# controller_board.net
KiCad netlist of a schematic drawn in EAGLE
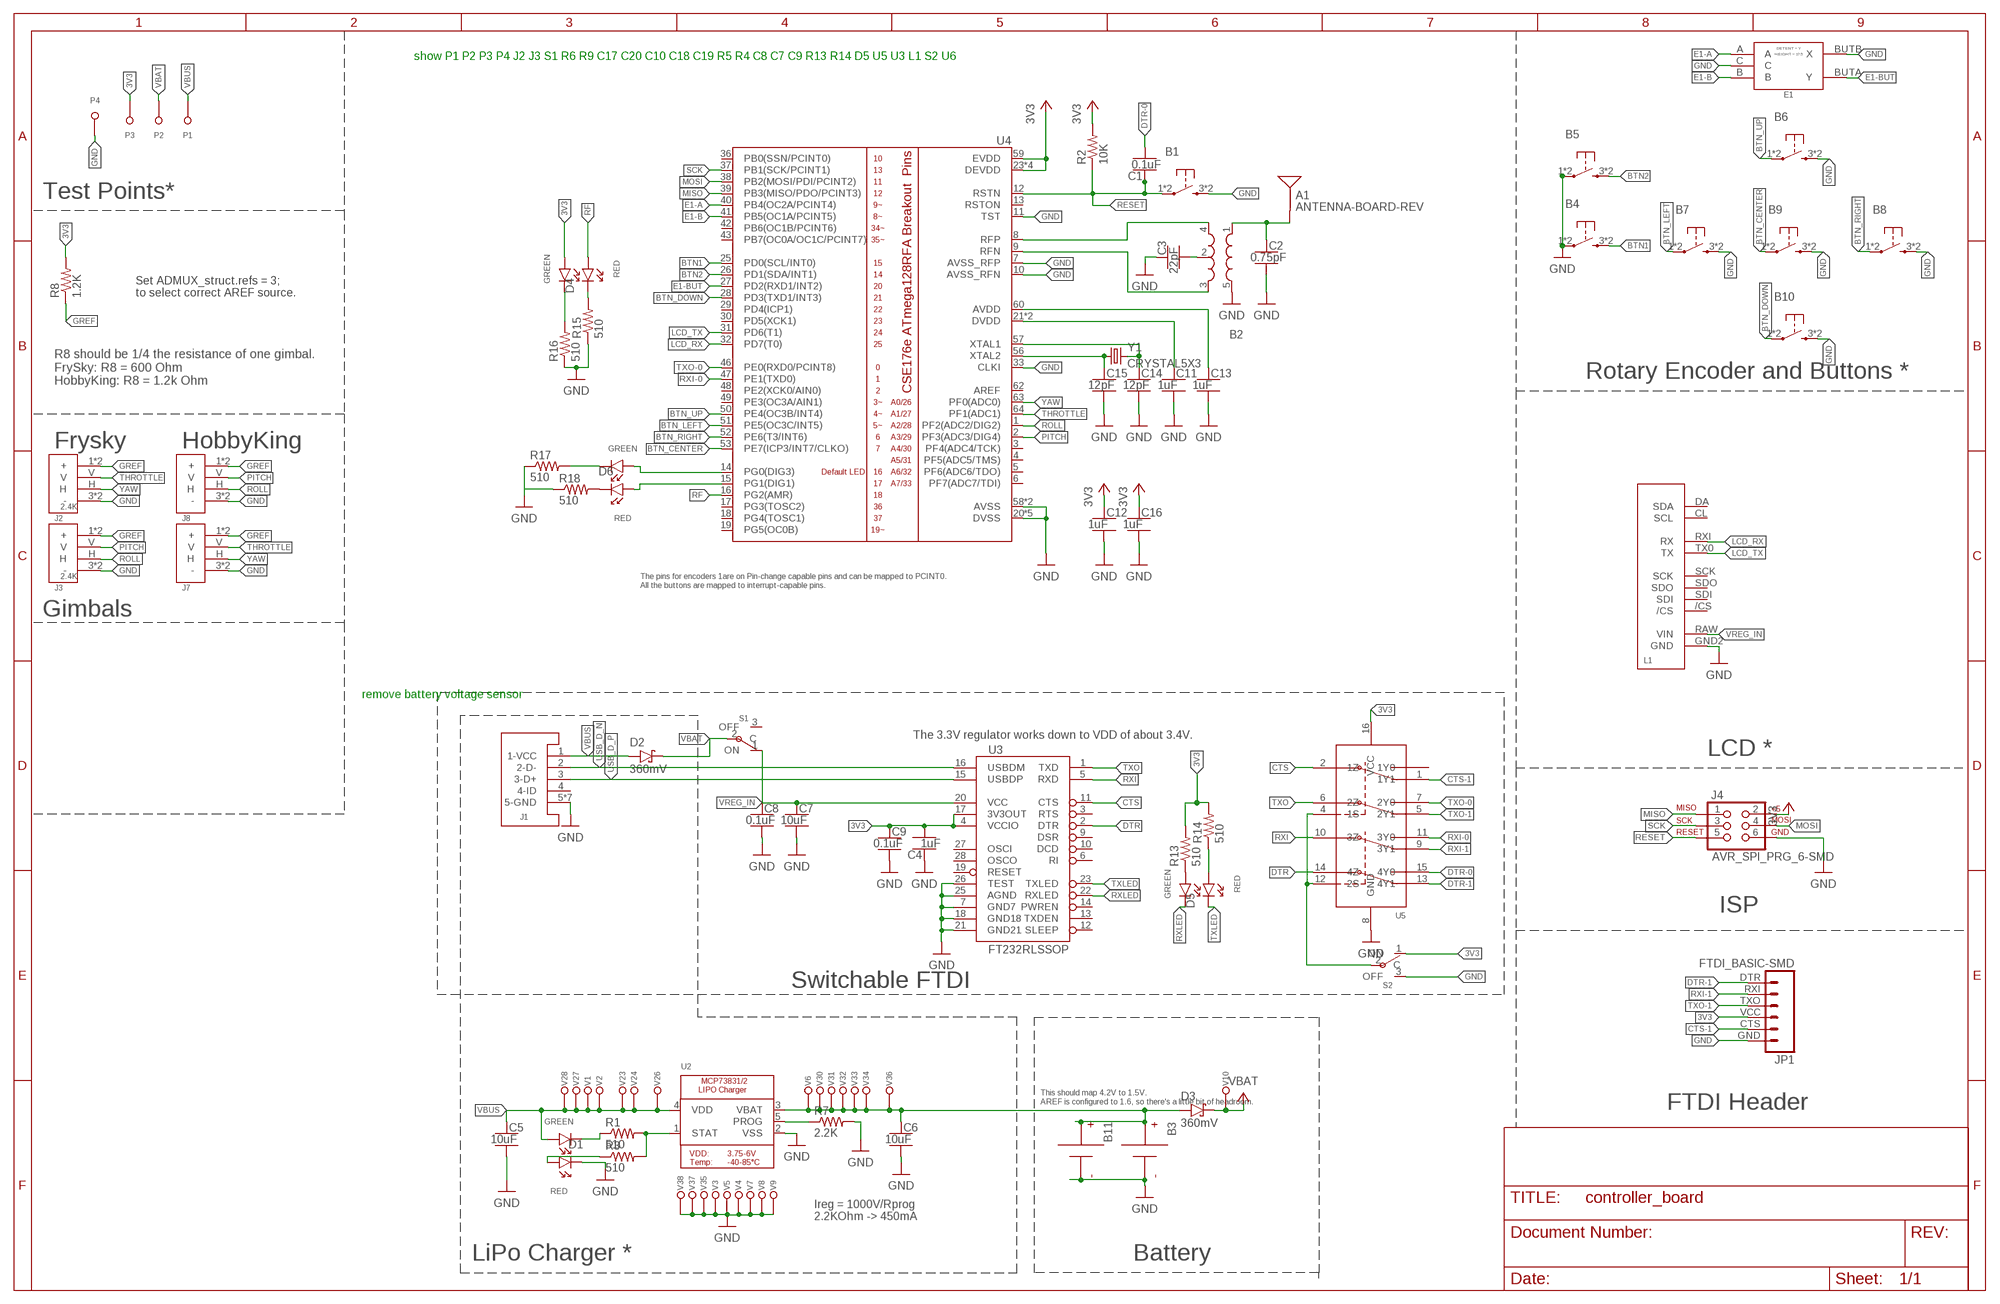
[diagram p0: schematic, sheet 1]

(export (version "E")
  (design (tool "Eeschema 10.0.6"))
  (components
    (comp (ref "A1")
      (value "ANTENNA-BOARD-REV")
      (footprint "eagle-import:ANT_PCB_2.4GHZ_NRF8001_1.6MM_1OZ_REV")
      (fields (field (name "CREATOR") "Swanson"))
      (libsource (lib "eagle-import") (part "ANTENNA-BOARD-REV"))
    )
    (comp (ref "B1")
      (value "PUSHBUTTON_-4.5X4.5")
      (footprint "eagle-import:4.5MM_TACTILE_SWITCH_TL3305AF160QG")
      (fields (field (name "CREATOR") "Swanson"))
      (libsource (lib "eagle-import") (part "PUSHBUTTON_-4.5X4.5"))
    )
    (comp (ref "B2")
      (value "BALUN0805")
      (footprint "eagle-import:BALUN")
      (fields
        (field (name "MFR") "Wurth Electronics Inc")
        (field (name "MPN") "748421245")
        (field (name "CREATOR") "Swanson")
        (field (name "REVIEWER") "Swanson")
      )
      (libsource (lib "eagle-import") (part "BALUN0805"))
    )
    (comp (ref "B3")
      (value "BATTERY-SPRING-SMD")
      (footprint "eagle-import:WIRE-TERMINAL-1X2-2.5MM-SMD-AVX-009276002021106")
      (libsource (lib "eagle-import") (part "BATTERY-SPRING-SMD"))
    )
    (comp (ref "B4")
      (value "PUSHBUTTON_-4.5X4.5")
      (footprint "eagle-import:4.5MM_TACTILE_SWITCH_TL3305AF160QG")
      (fields (field (name "CREATOR") "Swanson"))
      (libsource (lib "eagle-import") (part "PUSHBUTTON_-4.5X4.5"))
    )
    (comp (ref "B5")
      (value "PUSHBUTTON_-4.5X4.5")
      (footprint "eagle-import:4.5MM_TACTILE_SWITCH_TL3305AF160QG")
      (fields (field (name "CREATOR") "Swanson"))
      (libsource (lib "eagle-import") (part "PUSHBUTTON_-4.5X4.5"))
    )
    (comp (ref "B6")
      (value "PUSHBUTTON_-4.5X4.5")
      (footprint "eagle-import:4.5MM_TACTILE_SWITCH_TL3305AF160QG")
      (fields (field (name "CREATOR") "Swanson"))
      (libsource (lib "eagle-import") (part "PUSHBUTTON_-4.5X4.5"))
    )
    (comp (ref "B7")
      (value "PUSHBUTTON_-4.5X4.5")
      (footprint "eagle-import:4.5MM_TACTILE_SWITCH_TL3305AF160QG")
      (fields (field (name "CREATOR") "Swanson"))
      (libsource (lib "eagle-import") (part "PUSHBUTTON_-4.5X4.5"))
    )
    (comp (ref "B8")
      (value "PUSHBUTTON_-4.5X4.5")
      (footprint "eagle-import:4.5MM_TACTILE_SWITCH_TL3305AF160QG")
      (fields (field (name "CREATOR") "Swanson"))
      (libsource (lib "eagle-import") (part "PUSHBUTTON_-4.5X4.5"))
    )
    (comp (ref "B9")
      (value "PUSHBUTTON_-4.5X4.5")
      (footprint "eagle-import:4.5MM_TACTILE_SWITCH_TL3305AF160QG")
      (fields (field (name "CREATOR") "Swanson"))
      (libsource (lib "eagle-import") (part "PUSHBUTTON_-4.5X4.5"))
    )
    (comp (ref "B10")
      (value "PUSHBUTTON_-4.5X4.5")
      (footprint "eagle-import:4.5MM_TACTILE_SWITCH_TL3305AF160QG")
      (fields (field (name "CREATOR") "Swanson"))
      (libsource (lib "eagle-import") (part "PUSHBUTTON_-4.5X4.5"))
    )
    (comp (ref "B11")
      (value "BATTERY-SCREW-TERMINAL")
      (footprint "eagle-import:SCREW-TERMINAL-1X2-2.54MM")
      (fields (field (name "CREATOR") "Swanson"))
      (libsource (lib "eagle-import") (part "BATTERY-SCREW-TERMINAL"))
    )
    (comp (ref "C1")
      (value "0.1uF")
      (footprint "eagle-import:CAPC2012X140_HS")
      (fields
        (field (name "MFR") "TDK")
        (field (name "MPN") "C2012X7R2A104K125AA")
        (field (name "CREATOR") "Swanson")
        (field (name "REVIEWER") "Swanson")
      )
      (libsource (lib "eagle-import") (part "CAPACITOR-NP_SMD-2012-0805_CERAMIC-0.1UF"))
    )
    (comp (ref "C2")
      (value "0.75pF")
      (footprint "eagle-import:CAPC2012X140_HS")
      (fields
        (field (name "MFR") "Murata Electronics North America")
        (field (name "MPN") "GQM2195C2AR75CB01D")
        (field (name "CREATOR") "Swanson")
        (field (name "REVIEWER") "Swanson")
      )
      (libsource (lib "eagle-import") (part "CAPACITOR-NP_SMD-2012-0805_CERAMIC-0.75PF"))
    )
    (comp (ref "C3")
      (value "22pF")
      (footprint "eagle-import:CAPC2012X140_HS")
      (fields
        (field (name "MFR") "Murata Electronics North America")
        (field (name "MPN") "GRM21A5C2E220JW01D")
        (field (name "CREATOR") "Swanson")
        (field (name "REVIEWER") "Swanson")
      )
      (libsource (lib "eagle-import") (part "CAPACITOR-NP_SMD-2012-0805_CERAMIC-22PF"))
    )
    (comp (ref "C4")
      (value "1uF")
      (footprint "eagle-import:CAPC2012X140_HS")
      (fields
        (field (name "MFR") "Taiyo Yuden")
        (field (name "MPN") "TMK212B7105KG-T")
        (field (name "CREATOR") "Swanson")
        (field (name "REVIEWER") "Swanson")
      )
      (libsource (lib "eagle-import") (part "CAPACITOR-NP_SMD-2012-0805_CERAMIC-1UF"))
    )
    (comp (ref "C5")
      (value "10uF")
      (footprint "eagle-import:CAPC2012X140_HS")
      (fields (field (name "CREATOR") "Swanson") (field (name "REVIEWER") "Swanson"))
      (libsource (lib "eagle-import") (part "CAPACITOR-NP_SMD-2012-0805_CERAMIC-10UF"))
    )
    (comp (ref "C6")
      (value "10uF")
      (footprint "eagle-import:CAPC2012X140_HS")
      (fields (field (name "CREATOR") "Swanson") (field (name "REVIEWER") "Swanson"))
      (libsource (lib "eagle-import") (part "CAPACITOR-NP_SMD-2012-0805_CERAMIC-10UF"))
    )
    (comp (ref "C7")
      (value "10uF")
      (footprint "eagle-import:CAPC2012X140_HS")
      (fields (field (name "CREATOR") "Swanson") (field (name "REVIEWER") "Swanson"))
      (libsource (lib "eagle-import") (part "CAPACITOR-NP_SMD-2012-0805_CERAMIC-10UF"))
    )
    (comp (ref "C8")
      (value "0.1uF")
      (footprint "eagle-import:CAPC2012X140_HS")
      (fields
        (field (name "MFR") "TDK")
        (field (name "MPN") "C2012X7R2A104K125AA")
        (field (name "CREATOR") "Swanson")
        (field (name "REVIEWER") "Swanson")
      )
      (libsource (lib "eagle-import") (part "CAPACITOR-NP_SMD-2012-0805_CERAMIC-0.1UF"))
    )
    (comp (ref "C9")
      (value "0.1uF")
      (footprint "eagle-import:CAPC2012X140_HS")
      (fields
        (field (name "MFR") "TDK")
        (field (name "MPN") "C2012X7R2A104K125AA")
        (field (name "CREATOR") "Swanson")
        (field (name "REVIEWER") "Swanson")
      )
      (libsource (lib "eagle-import") (part "CAPACITOR-NP_SMD-2012-0805_CERAMIC-0.1UF"))
    )
    (comp (ref "C11")
      (value "1uF")
      (footprint "eagle-import:CAPC2012X140_HS")
      (fields
        (field (name "MFR") "Taiyo Yuden")
        (field (name "MPN") "TMK212B7105KG-T")
        (field (name "CREATOR") "Swanson")
        (field (name "REVIEWER") "Swanson")
      )
      (libsource (lib "eagle-import") (part "CAPACITOR-NP_SMD-2012-0805_CERAMIC-1UF"))
    )
    (comp (ref "C12")
      (value "1uF")
      (footprint "eagle-import:CAPC2012X140_HS")
      (fields
        (field (name "MFR") "Taiyo Yuden")
        (field (name "MPN") "TMK212B7105KG-T")
        (field (name "CREATOR") "Swanson")
        (field (name "REVIEWER") "Swanson")
      )
      (libsource (lib "eagle-import") (part "CAPACITOR-NP_SMD-2012-0805_CERAMIC-1UF"))
    )
    (comp (ref "C13")
      (value "1uF")
      (footprint "eagle-import:CAPC2012X140_HS")
      (fields
        (field (name "MFR") "Taiyo Yuden")
        (field (name "MPN") "TMK212B7105KG-T")
        (field (name "CREATOR") "Swanson")
        (field (name "REVIEWER") "Swanson")
      )
      (libsource (lib "eagle-import") (part "CAPACITOR-NP_SMD-2012-0805_CERAMIC-1UF"))
    )
    (comp (ref "C14")
      (value "12pF")
      (footprint "eagle-import:CAPC2012X140_HS")
      (fields
        (field (name "MFR") "Murata Electronics North America")
        (field (name "MPN") "GRM21A5C2E120JW01D")
        (field (name "CREATOR") "Swanson")
        (field (name "REVIEWER") "Swanson")
      )
      (libsource (lib "eagle-import") (part "CAPACITOR-NP_SMD-2012-0805_CERAMIC-12PF"))
    )
    (comp (ref "C15")
      (value "12pF")
      (footprint "eagle-import:CAPC2012X140_HS")
      (fields
        (field (name "MFR") "Murata Electronics North America")
        (field (name "MPN") "GRM21A5C2E120JW01D")
        (field (name "CREATOR") "Swanson")
        (field (name "REVIEWER") "Swanson")
      )
      (libsource (lib "eagle-import") (part "CAPACITOR-NP_SMD-2012-0805_CERAMIC-12PF"))
    )
    (comp (ref "C16")
      (value "1uF")
      (footprint "eagle-import:CAPC2012X140_HS")
      (fields
        (field (name "MFR") "Taiyo Yuden")
        (field (name "MPN") "TMK212B7105KG-T")
        (field (name "CREATOR") "Swanson")
        (field (name "REVIEWER") "Swanson")
      )
      (libsource (lib "eagle-import") (part "CAPACITOR-NP_SMD-2012-0805_CERAMIC-1UF"))
    )
    (comp (ref "D1")
      (value "LED-2X-GREEN/RED")
      (footprint "eagle-import:LED-2X-LTST-C155")
      (fields
        (field (name "COLOR2") "RED")
        (field (name "COLOR1") "GREEN")
        (field (name "CREATOR") "Swanson")
      )
      (libsource (lib "eagle-import") (part "LED-2X-GREEN/RED"))
    )
    (comp (ref "D2")
      (value "360mV")
      (footprint "eagle-import:SOD3716X135_HS")
      (fields
        (field (name "MFR") "Toshiba Semiconductor and Storage")
        (field (name "MPN") "CRS08(TE85L,Q,M)")
        (field (name "CREATOR") "Swanson")
        (field (name "REVIEWER") "Swanson")
      )
      (libsource (lib "eagle-import") (part "DIODE-SCHOTTKY_SMD-SOD123-360MV"))
    )
    (comp (ref "D3")
      (value "360mV")
      (footprint "eagle-import:SOD3716X135_HS")
      (fields
        (field (name "MFR") "Toshiba Semiconductor and Storage")
        (field (name "MPN") "CRS08(TE85L,Q,M)")
        (field (name "CREATOR") "Swanson")
        (field (name "REVIEWER") "Swanson")
      )
      (libsource (lib "eagle-import") (part "DIODE-SCHOTTKY_SMD-SOD123-360MV"))
    )
    (comp (ref "D4")
      (value "LED-2X-GREEN/RED")
      (footprint "eagle-import:LED-2X-LTST-C155")
      (fields
        (field (name "COLOR2") "RED")
        (field (name "COLOR1") "GREEN")
        (field (name "CREATOR") "Swanson")
      )
      (libsource (lib "eagle-import") (part "LED-2X-GREEN/RED"))
    )
    (comp (ref "D5")
      (value "LED-2X-GREEN/RED")
      (footprint "eagle-import:LED-2X-LTST-C155")
      (fields
        (field (name "COLOR2") "RED")
        (field (name "COLOR1") "GREEN")
        (field (name "CREATOR") "Swanson")
      )
      (libsource (lib "eagle-import") (part "LED-2X-GREEN/RED"))
    )
    (comp (ref "D6")
      (value "LED-2X-GREEN/RED")
      (footprint "eagle-import:LED-2X-LTST-C155")
      (fields
        (field (name "COLOR2") "RED")
        (field (name "COLOR1") "GREEN")
        (field (name "CREATOR") "Swanson")
      )
      (libsource (lib "eagle-import") (part "LED-2X-GREEN/RED"))
    )
    (comp (ref "E1")
      (value "ROTARY-ENCODER-W/BUTTON-BOURNS-PEC12R-4217F")
      (footprint "eagle-import:BOURNS-PEC12R")
      (fields (field (name "DETENT") "Y") (field (name "HEIGHT") "17.5") (field (name "CREATOR") "Swanson"))
      (libsource (lib "eagle-import") (part "ROTARY-ENCODER-W/BUTTON-BOURNS-PEC12R-4217F"))
    )
    (comp (ref "J1")
      (value "USB-MICROA-AMPHENOL-10118192-0001LF")
      (footprint "eagle-import:USB-MICROA-10118192-0001LF")
      (fields (field (name "CREATOR") "Swanson"))
      (libsource (lib "eagle-import") (part "USB-MICROA-AMPHENOL-10118192-0001LF"))
    )
    (comp (ref "J2")
      (value "2.4K")
      (footprint "eagle-import:JST-13-PTH")
      (fields (field (name "CREATOR") "Swanson"))
      (libsource (lib "eagle-import") (part "FRSKY-GIMBAL-FRYSKY"))
    )
    (comp (ref "J3")
      (value "2.4K")
      (footprint "eagle-import:JST-13-PTH")
      (fields (field (name "SPICEPREFIX") "E") (field (name "CREATOR") "Swanson"))
      (libsource (lib "eagle-import") (part "FRSKY-GIMBAL-FRYSKY"))
    )
    (comp (ref "J4")
      (value "AVR_SPI_PRG_6-SMD")
      (footprint "eagle-import:2X3-SMD")
      (fields (field (name "CREATOR") "Swanson"))
      (libsource (lib "eagle-import") (part "AVR_SPI_PRG_6-SMD"))
    )
    (comp (ref "J7")
      (value "FRSKY-GIMBAL-2X-SERVO-SMD")
      (footprint "eagle-import:2X-SERVO-SMD")
      (libsource (lib "eagle-import") (part "FRSKY-GIMBAL-2X-SERVO-SMD"))
    )
    (comp (ref "J8")
      (value "FRSKY-GIMBAL-2X-SERVO-SMD")
      (footprint "eagle-import:2X-SERVO-SMD")
      (libsource (lib "eagle-import") (part "FRSKY-GIMBAL-2X-SERVO-SMD"))
    )
    (comp (ref "JP1")
      (value "FTDI_BASIC-SMD")
      (footprint "eagle-import:FTDI-BASIC-SMD")
      (libsource (lib "eagle-import") (part "FTDI_BASIC-SMD"))
    )
    (comp (ref "L1")
      (value "SPARKFUN_SERLCD_SERIAL_REDUCED-SMD")
      (footprint "eagle-import:SPARKFUN_SERLCD_16X2_REDUCED_SMD")
      (fields (field (name "CREATOR") "Swanson"))
      (libsource (lib "eagle-import") (part "SPARKFUN_SERLCD_SERIAL_REDUCED-SMD"))
    )
    (comp (ref "P1")
      (value "TEST-POINT")
      (footprint "eagle-import:TEST-POINT-KEYSTONE-5000")
      (fields (field (name "CREATOR") "Swanson"))
      (libsource (lib "eagle-import") (part "TEST-POINT"))
    )
    (comp (ref "P2")
      (value "TEST-POINT")
      (footprint "eagle-import:TEST-POINT-KEYSTONE-5000")
      (fields (field (name "CREATOR") "Swanson"))
      (libsource (lib "eagle-import") (part "TEST-POINT"))
    )
    (comp (ref "P3")
      (value "TEST-POINT")
      (footprint "eagle-import:TEST-POINT-KEYSTONE-5000")
      (fields (field (name "CREATOR") "Swanson"))
      (libsource (lib "eagle-import") (part "TEST-POINT"))
    )
    (comp (ref "P4")
      (value "TEST-POINT")
      (footprint "eagle-import:TEST-POINT-KEYSTONE-5000")
      (fields (field (name "CREATOR") "Swanson"))
      (libsource (lib "eagle-import") (part "TEST-POINT"))
    )
    (comp (ref "R1")
      (value "510")
      (footprint "eagle-import:RESC2012X60_HS")
      (fields (field (name "CREATOR") "SWANSON"))
      (libsource (lib "eagle-import") (part "RESISTOR_SMD-2012-0805-510"))
    )
    (comp (ref "R2")
      (value "10K")
      (footprint "eagle-import:RESC2012X60_HS")
      (fields
        (field (name "MFR") "Yageo")
        (field (name "MPN") "RC0805JR-0710KL")
        (field (name "CREATOR") "Swanson")
        (field (name "REVIEWER") "Swanson")
      )
      (libsource (lib "eagle-import") (part "RESISTOR_SMD-2012-0805-10K"))
    )
    (comp (ref "R3")
      (value "510")
      (footprint "eagle-import:RESC2012X60_HS")
      (fields (field (name "CREATOR") "SWANSON"))
      (libsource (lib "eagle-import") (part "RESISTOR_SMD-2012-0805-510"))
    )
    (comp (ref "R7")
      (value "2.2K")
      (footprint "eagle-import:RESC2012X60_HS")
      (fields (field (name "CREATOR") "SWANSON"))
      (libsource (lib "eagle-import") (part "RESISTOR_SMD-2012-0805-2.2K"))
    )
    (comp (ref "R8")
      (value "1.2K")
      (footprint "eagle-import:RESC2012X60_HS")
      (fields (field (name "CREATOR") "Swanson"))
      (libsource (lib "eagle-import") (part "RESISTOR_SMD-2012-0805-1.2K"))
    )
    (comp (ref "R13")
      (value "510")
      (footprint "eagle-import:RESC2012X60_HS")
      (fields (field (name "CREATOR") "SWANSON"))
      (libsource (lib "eagle-import") (part "RESISTOR_SMD-2012-0805-510"))
    )
    (comp (ref "R14")
      (value "510")
      (footprint "eagle-import:RESC2012X60_HS")
      (fields (field (name "CREATOR") "SWANSON"))
      (libsource (lib "eagle-import") (part "RESISTOR_SMD-2012-0805-510"))
    )
    (comp (ref "R15")
      (value "510")
      (footprint "eagle-import:RESC2012X60_HS")
      (fields (field (name "CREATOR") "SWANSON"))
      (libsource (lib "eagle-import") (part "RESISTOR_SMD-2012-0805-510"))
    )
    (comp (ref "R16")
      (value "510")
      (footprint "eagle-import:RESC2012X60_HS")
      (fields (field (name "CREATOR") "SWANSON"))
      (libsource (lib "eagle-import") (part "RESISTOR_SMD-2012-0805-510"))
    )
    (comp (ref "R17")
      (value "510")
      (footprint "eagle-import:RESC2012X60_HS")
      (fields (field (name "CREATOR") "SWANSON"))
      (libsource (lib "eagle-import") (part "RESISTOR_SMD-2012-0805-510"))
    )
    (comp (ref "R18")
      (value "510")
      (footprint "eagle-import:RESC2012X60_HS")
      (fields (field (name "CREATOR") "SWANSON"))
      (libsource (lib "eagle-import") (part "RESISTOR_SMD-2012-0805-510"))
    )
    (comp (ref "S1")
      (value "POWER-SWITCH-MFS201N-9-Z-SMD-VERTICAL")
      (footprint "eagle-import:JS102011JCQN")
      (fields (field (name "CREATOR") "Swanson"))
      (libsource (lib "eagle-import") (part "POWER-SWITCH-MFS201N-9-Z-SMD-VERTICAL"))
    )
    (comp (ref "S2")
      (value "POWER-SWITCH-MFS201N-9-Z-SMD-VERTICAL")
      (footprint "eagle-import:JS102011JCQN")
      (fields (field (name "CREATOR") "Swanson"))
      (libsource (lib "eagle-import") (part "POWER-SWITCH-MFS201N-9-Z-SMD-VERTICAL"))
    )
    (comp (ref "U2")
      (value "MCP73831T-2ACI/OT")
      (footprint "eagle-import:SOT23-5")
      (fields (field (name "CREATOR") "Adafruit"))
      (libsource (lib "eagle-import") (part "MCP73831/2"))
    )
    (comp (ref "U3")
      (value "FT232RLSSOP")
      (footprint "eagle-import:SSOP28DB")
      (fields (field (name "CREATOR") "Swanson"))
      (libsource (lib "eagle-import") (part "FT232RLSSOP"))
    )
    (comp (ref "U4")
      (value "ATMEGA128RFA1")
      (footprint "eagle-import:QFN-64")
      (fields
        (field (name "MFR") "Atmel")
        (field (name "MPN") "ATMEGA128RFA1-ZUR00")
        (field (name "CREATOR") "Swanson")
        (field (name "REVIEWER") "Swanson")
      )
      (libsource (lib "eagle-import") (part "ATMEGA128RFA1"))
    )
    (comp (ref "U5")
      (value "DPDT-X2")
      (footprint "eagle-import:SOP65P640X110-16")
      (fields (field (name "CREATOR") "Swanson"))
      (libsource (lib "eagle-import") (part "DPDT-X2"))
    )
    (comp (ref "V1")
      (value "LOCKED-VIA-0.2")
      (footprint "eagle-import:VIA-0.2MM")
      (fields (field (name "CREATOR") "Swanson"))
      (libsource (lib "eagle-import") (part "LOCKED-VIA-0.2"))
    )
    (comp (ref "V2")
      (value "LOCKED-VIA-0.2")
      (footprint "eagle-import:VIA-0.2MM")
      (fields (field (name "CREATOR") "Swanson"))
      (libsource (lib "eagle-import") (part "LOCKED-VIA-0.2"))
    )
    (comp (ref "V3")
      (value "LOCKED-VIA-0.2")
      (footprint "eagle-import:VIA-0.2MM")
      (fields (field (name "CREATOR") "Swanson"))
      (libsource (lib "eagle-import") (part "LOCKED-VIA-0.2"))
    )
    (comp (ref "V4")
      (value "LOCKED-VIA-0.2")
      (footprint "eagle-import:VIA-0.2MM")
      (fields (field (name "CREATOR") "Swanson"))
      (libsource (lib "eagle-import") (part "LOCKED-VIA-0.2"))
    )
    (comp (ref "V5")
      (value "LOCKED-VIA-0.2")
      (footprint "eagle-import:VIA-0.2MM")
      (fields (field (name "CREATOR") "Swanson"))
      (libsource (lib "eagle-import") (part "LOCKED-VIA-0.2"))
    )
    (comp (ref "V6")
      (value "LOCKED-VIA-0.2")
      (footprint "eagle-import:VIA-0.2MM")
      (fields (field (name "CREATOR") "Swanson"))
      (libsource (lib "eagle-import") (part "LOCKED-VIA-0.2"))
    )
    (comp (ref "V7")
      (value "LOCKED-VIA-0.2")
      (footprint "eagle-import:VIA-0.2MM")
      (fields (field (name "CREATOR") "Swanson"))
      (libsource (lib "eagle-import") (part "LOCKED-VIA-0.2"))
    )
    (comp (ref "V8")
      (value "LOCKED-VIA-0.2")
      (footprint "eagle-import:VIA-0.2MM")
      (fields (field (name "CREATOR") "Swanson"))
      (libsource (lib "eagle-import") (part "LOCKED-VIA-0.2"))
    )
    (comp (ref "V9")
      (value "LOCKED-VIA-0.2")
      (footprint "eagle-import:VIA-0.2MM")
      (fields (field (name "CREATOR") "Swanson"))
      (libsource (lib "eagle-import") (part "LOCKED-VIA-0.2"))
    )
    (comp (ref "V10")
      (value "LOCKED-VIA-0.2")
      (footprint "eagle-import:VIA-0.2MM")
      (fields (field (name "CREATOR") "Swanson"))
      (libsource (lib "eagle-import") (part "LOCKED-VIA-0.2"))
    )
    (comp (ref "V23")
      (value "LOCKED-VIA-0.2")
      (footprint "eagle-import:VIA-0.2MM")
      (fields (field (name "CREATOR") "Swanson"))
      (libsource (lib "eagle-import") (part "LOCKED-VIA-0.2"))
    )
    (comp (ref "V24")
      (value "LOCKED-VIA-0.2")
      (footprint "eagle-import:VIA-0.2MM")
      (fields (field (name "CREATOR") "Swanson"))
      (libsource (lib "eagle-import") (part "LOCKED-VIA-0.2"))
    )
    (comp (ref "V26")
      (value "LOCKED-VIA-0.2")
      (footprint "eagle-import:VIA-0.2MM")
      (fields (field (name "CREATOR") "Swanson"))
      (libsource (lib "eagle-import") (part "LOCKED-VIA-0.2"))
    )
    (comp (ref "V27")
      (value "LOCKED-VIA-0.2")
      (footprint "eagle-import:VIA-0.2MM")
      (fields (field (name "CREATOR") "Swanson"))
      (libsource (lib "eagle-import") (part "LOCKED-VIA-0.2"))
    )
    (comp (ref "V28")
      (value "LOCKED-VIA-0.2")
      (footprint "eagle-import:VIA-0.2MM")
      (fields (field (name "CREATOR") "Swanson"))
      (libsource (lib "eagle-import") (part "LOCKED-VIA-0.2"))
    )
    (comp (ref "V30")
      (value "LOCKED-VIA-0.2")
      (footprint "eagle-import:VIA-0.2MM")
      (fields (field (name "CREATOR") "Swanson"))
      (libsource (lib "eagle-import") (part "LOCKED-VIA-0.2"))
    )
    (comp (ref "V31")
      (value "LOCKED-VIA-0.2")
      (footprint "eagle-import:VIA-0.2MM")
      (fields (field (name "CREATOR") "Swanson"))
      (libsource (lib "eagle-import") (part "LOCKED-VIA-0.2"))
    )
    (comp (ref "V32")
      (value "LOCKED-VIA-0.2")
      (footprint "eagle-import:VIA-0.2MM")
      (fields (field (name "CREATOR") "Swanson"))
      (libsource (lib "eagle-import") (part "LOCKED-VIA-0.2"))
    )
    (comp (ref "V33")
      (value "LOCKED-VIA-0.2")
      (footprint "eagle-import:VIA-0.2MM")
      (fields (field (name "CREATOR") "Swanson"))
      (libsource (lib "eagle-import") (part "LOCKED-VIA-0.2"))
    )
    (comp (ref "V34")
      (value "LOCKED-VIA-0.2")
      (footprint "eagle-import:VIA-0.2MM")
      (fields (field (name "CREATOR") "Swanson"))
      (libsource (lib "eagle-import") (part "LOCKED-VIA-0.2"))
    )
    (comp (ref "V35")
      (value "LOCKED-VIA-0.2")
      (footprint "eagle-import:VIA-0.2MM")
      (fields (field (name "CREATOR") "Swanson"))
      (libsource (lib "eagle-import") (part "LOCKED-VIA-0.2"))
    )
    (comp (ref "V36")
      (value "LOCKED-VIA-0.2")
      (footprint "eagle-import:VIA-0.2MM")
      (fields (field (name "CREATOR") "Swanson"))
      (libsource (lib "eagle-import") (part "LOCKED-VIA-0.2"))
    )
    (comp (ref "V37")
      (value "LOCKED-VIA-0.2")
      (footprint "eagle-import:VIA-0.2MM")
      (fields (field (name "CREATOR") "Swanson"))
      (libsource (lib "eagle-import") (part "LOCKED-VIA-0.2"))
    )
    (comp (ref "V38")
      (value "LOCKED-VIA-0.2")
      (footprint "eagle-import:VIA-0.2MM")
      (fields (field (name "CREATOR") "Swanson"))
      (libsource (lib "eagle-import") (part "LOCKED-VIA-0.2"))
    )
    (comp (ref "Y1")
      (value "CRYSTAL5X3")
      (footprint "eagle-import:CRYSTAL-SMD-5X3")
      (fields
        (field (name "MFR") "Abracon LLC")
        (field (name "MPN") "ABM3B-16.000MHZ-B2-T")
        (field (name "CREATOR") "Swanson")
        (field (name "REVIEWER") "Swanson")
      )
      (libsource (lib "eagle-import") (part "CRYSTAL5X3"))
    )
  )
  (nets
    (net (code "1") (name "3V3") (class "Default")
      (node (ref "C12") (pin "1") (pinfunction "1_1") (pintype "passive"))
      (node (ref "C16") (pin "1") (pinfunction "1_1") (pintype "passive"))
      (node (ref "C4") (pin "2") (pinfunction "2_2") (pintype "passive"))
      (node (ref "C9") (pin "1") (pinfunction "1_1") (pintype "passive"))
      (node (ref "D4") (pin "A2") (pinfunction "A2_A2") (pintype "passive"))
      (node (ref "J4") (pin "2") (pinfunction "2_2") (pintype "passive"))
      (node (ref "JP1") (pin "VCC") (pinfunction "4_VCC") (pintype "passive"))
      (node (ref "P3") (pin "T") (pinfunction "T_T") (pintype "bidirectional"))
      (node (ref "R13") (pin "2") (pinfunction "2_2") (pintype "passive"))
      (node (ref "R14") (pin "2") (pinfunction "2_2") (pintype "passive"))
      (node (ref "R2") (pin "2") (pinfunction "2_2") (pintype "passive"))
      (node (ref "R8") (pin "2") (pinfunction "2_2") (pintype "passive"))
      (node (ref "S2") (pin "1") (pinfunction "ON_1") (pintype "bidirectional"))
      (node (ref "U3") (pin "17") (pinfunction "3V3OUT_17") (pintype "output"))
      (node (ref "U3") (pin "4") (pinfunction "VCCIO_4") (pintype "power_in"))
      (node (ref "U4") (pin "23") (pinfunction "DEVDD_23") (pintype "bidirectional"))
      (node (ref "U4") (pin "34") (pinfunction "DEVDD_34") (pintype "bidirectional"))
      (node (ref "U4") (pin "44") (pinfunction "DEVDD_44") (pintype "bidirectional"))
      (node (ref "U4") (pin "54") (pinfunction "DEVDD_54") (pintype "bidirectional"))
      (node (ref "U4") (pin "59") (pinfunction "EVDD_59") (pintype "bidirectional"))
      (node (ref "U5") (pin "16") (pinfunction "VCC_16") (pintype "bidirectional"))
    )
    (net (code "2") (name "BTN1") (class "Default")
      (node (ref "B4") (pin "3") (pinfunction "2_3") (pintype "passive"))
      (node (ref "B4") (pin "4") (pinfunction "2_4") (pintype "passive"))
      (node (ref "U4") (pin "25") (pinfunction "PD0(SCL/INT0)_25") (pintype "bidirectional"))
    )
    (net (code "3") (name "BTN2") (class "Default")
      (node (ref "B5") (pin "3") (pinfunction "2_3") (pintype "passive"))
      (node (ref "B5") (pin "4") (pinfunction "2_4") (pintype "passive"))
      (node (ref "U4") (pin "26") (pinfunction "PD1(SDA/INT1)_26") (pintype "bidirectional"))
    )
    (net (code "4") (name "BTN_CENTER") (class "Default")
      (node (ref "B9") (pin "1") (pinfunction "1_1") (pintype "passive"))
      (node (ref "B9") (pin "2") (pinfunction "1_2") (pintype "passive"))
      (node (ref "U4") (pin "53") (pinfunction "PE7(ICP3/INT7/CLKO)_53") (pintype "bidirectional"))
    )
    (net (code "5") (name "BTN_DOWN") (class "Default")
      (node (ref "B10") (pin "1") (pinfunction "1_1") (pintype "passive"))
      (node (ref "B10") (pin "2") (pinfunction "1_2") (pintype "passive"))
      (node (ref "U4") (pin "28") (pinfunction "PD3(TXD1/INT3)_28") (pintype "bidirectional"))
    )
    (net (code "6") (name "BTN_LEFT") (class "Default")
      (node (ref "B7") (pin "1") (pinfunction "1_1") (pintype "passive"))
      (node (ref "B7") (pin "2") (pinfunction "1_2") (pintype "passive"))
      (node (ref "U4") (pin "51") (pinfunction "PE5(OC3C/INT5)_51") (pintype "bidirectional"))
    )
    (net (code "7") (name "BTN_RIGHT") (class "Default")
      (node (ref "B8") (pin "1") (pinfunction "1_1") (pintype "passive"))
      (node (ref "B8") (pin "2") (pinfunction "1_2") (pintype "passive"))
      (node (ref "U4") (pin "52") (pinfunction "PE6(T3/INT6)_52") (pintype "bidirectional"))
    )
    (net (code "8") (name "BTN_UP") (class "Default")
      (node (ref "B6") (pin "1") (pinfunction "1_1") (pintype "passive"))
      (node (ref "B6") (pin "2") (pinfunction "1_2") (pintype "passive"))
      (node (ref "U4") (pin "50") (pinfunction "PE4(OC3B/INT4)_50") (pintype "bidirectional"))
    )
    (net (code "9") (name "CTS") (class "Default")
      (node (ref "U3") (pin "11") (pinfunction "CTS_11") (pintype "input"))
      (node (ref "U5") (pin "2") (pinfunction "1Z_2") (pintype "bidirectional"))
    )
    (net (code "10") (name "CTS-1") (class "Default")
      (node (ref "JP1") (pin "CTS") (pinfunction "5_CTS") (pintype "passive"))
      (node (ref "U5") (pin "1") (pinfunction "1Y1_1") (pintype "bidirectional"))
    )
    (net (code "11") (name "DTR") (class "Default")
      (node (ref "U3") (pin "2") (pinfunction "DTR_2") (pintype "output"))
      (node (ref "U5") (pin "14") (pinfunction "4Z_14") (pintype "bidirectional"))
    )
    (net (code "12") (name "DTR-0") (class "Default")
      (node (ref "C1") (pin "2") (pinfunction "2_2") (pintype "passive"))
      (node (ref "U5") (pin "15") (pinfunction "4Y0_15") (pintype "bidirectional"))
    )
    (net (code "13") (name "DTR-1") (class "Default")
      (node (ref "JP1") (pin "DTR") (pinfunction "1_DTR") (pintype "passive"))
      (node (ref "U5") (pin "13") (pinfunction "4Y1_13") (pintype "bidirectional"))
    )
    (net (code "14") (name "E1-A") (class "Default")
      (node (ref "E1") (pin "A") (pinfunction "A_A") (pintype "bidirectional"))
      (node (ref "U4") (pin "40") (pinfunction "PB4(OC2A/PCINT4)_40") (pintype "bidirectional"))
    )
    (net (code "15") (name "E1-B") (class "Default")
      (node (ref "E1") (pin "B") (pinfunction "B_B") (pintype "bidirectional"))
      (node (ref "U4") (pin "41") (pinfunction "PB5(OC1A/PCINT5)_41") (pintype "bidirectional"))
    )
    (net (code "16") (name "E1-BUT") (class "Default")
      (node (ref "E1") (pin "BUTA") (pinfunction "Y_BUTA") (pintype "bidirectional"))
      (node (ref "U4") (pin "27") (pinfunction "PD2(RXD1/INT2)_27") (pintype "bidirectional"))
    )
    (net (code "17") (name "GND") (class "Default")
      (node (ref "B1") (pin "3") (pinfunction "2_3") (pintype "passive"))
      (node (ref "B1") (pin "4") (pinfunction "2_4") (pintype "passive"))
      (node (ref "B10") (pin "3") (pinfunction "2_3") (pintype "passive"))
      (node (ref "B10") (pin "4") (pinfunction "2_4") (pintype "passive"))
      (node (ref "B11") (pin "1") (pinfunction "N_1") (pintype "bidirectional"))
      (node (ref "B2") (pin "5") (pinfunction "GND_5") (pintype "bidirectional"))
      (node (ref "B3") (pin "2A") (pinfunction "N_2A") (pintype "bidirectional"))
      (node (ref "B3") (pin "2B") (pinfunction "N_2B") (pintype "bidirectional"))
      (node (ref "B4") (pin "1") (pinfunction "1_1") (pintype "passive"))
      (node (ref "B4") (pin "2") (pinfunction "1_2") (pintype "passive"))
      (node (ref "B5") (pin "1") (pinfunction "1_1") (pintype "passive"))
      (node (ref "B5") (pin "2") (pinfunction "1_2") (pintype "passive"))
      (node (ref "B6") (pin "3") (pinfunction "2_3") (pintype "passive"))
      (node (ref "B6") (pin "4") (pinfunction "2_4") (pintype "passive"))
      (node (ref "B7") (pin "3") (pinfunction "2_3") (pintype "passive"))
      (node (ref "B7") (pin "4") (pinfunction "2_4") (pintype "passive"))
      (node (ref "B8") (pin "3") (pinfunction "2_3") (pintype "passive"))
      (node (ref "B8") (pin "4") (pinfunction "2_4") (pintype "passive"))
      (node (ref "B9") (pin "3") (pinfunction "2_3") (pintype "passive"))
      (node (ref "B9") (pin "4") (pinfunction "2_4") (pintype "passive"))
      (node (ref "C11") (pin "2") (pinfunction "2_2") (pintype "passive"))
      (node (ref "C12") (pin "2") (pinfunction "2_2") (pintype "passive"))
      (node (ref "C13") (pin "2") (pinfunction "2_2") (pintype "passive"))
      (node (ref "C14") (pin "2") (pinfunction "2_2") (pintype "passive"))
      (node (ref "C15") (pin "2") (pinfunction "2_2") (pintype "passive"))
      (node (ref "C16") (pin "2") (pinfunction "2_2") (pintype "passive"))
      (node (ref "C2") (pin "2") (pinfunction "2_2") (pintype "passive"))
      (node (ref "C3") (pin "1") (pinfunction "1_1") (pintype "passive"))
      (node (ref "C4") (pin "1") (pinfunction "1_1") (pintype "passive"))
      (node (ref "C5") (pin "2") (pinfunction "2_2") (pintype "passive"))
      (node (ref "C6") (pin "2") (pinfunction "2_2") (pintype "passive"))
      (node (ref "C7") (pin "2") (pinfunction "2_2") (pintype "passive"))
      (node (ref "C8") (pin "2") (pinfunction "2_2") (pintype "passive"))
      (node (ref "C9") (pin "2") (pinfunction "2_2") (pintype "passive"))
      (node (ref "D1") (pin "C1") (pinfunction "C1_C1") (pintype "passive"))
      (node (ref "E1") (pin "BUTB") (pinfunction "X_BUTB") (pintype "bidirectional"))
      (node (ref "E1") (pin "C") (pinfunction "C_C") (pintype "bidirectional"))
      (node (ref "J1") (pin "10") (pinfunction "5-GND_10") (pintype "bidirectional"))
      (node (ref "J1") (pin "11") (pinfunction "5-GND_11") (pintype "bidirectional"))
      (node (ref "J1") (pin "5") (pinfunction "5-GND_5") (pintype "bidirectional"))
      (node (ref "J1") (pin "6") (pinfunction "5-GND_6") (pintype "bidirectional"))
      (node (ref "J1") (pin "7") (pinfunction "5-GND_7") (pintype "bidirectional"))
      (node (ref "J1") (pin "8") (pinfunction "5-GND_8") (pintype "bidirectional"))
      (node (ref "J1") (pin "9") (pinfunction "5-GND_9") (pintype "bidirectional"))
      (node (ref "J2") (pin "3") (pinfunction "-_3") (pintype "bidirectional"))
      (node (ref "J2") (pin "6") (pinfunction "-_6") (pintype "bidirectional"))
      (node (ref "J3") (pin "3") (pinfunction "-_3") (pintype "bidirectional"))
      (node (ref "J3") (pin "6") (pinfunction "-_6") (pintype "bidirectional"))
      (node (ref "J4") (pin "6") (pinfunction "6_6") (pintype "passive"))
      (node (ref "J7") (pin "3") (pinfunction "-_3") (pintype "bidirectional"))
      (node (ref "J7") (pin "6") (pinfunction "-_6") (pintype "bidirectional"))
      (node (ref "J8") (pin "3") (pinfunction "-_3") (pintype "bidirectional"))
      (node (ref "J8") (pin "6") (pinfunction "-_6") (pintype "bidirectional"))
      (node (ref "JP1") (pin "GND") (pinfunction "6_GND") (pintype "passive"))
      (node (ref "L1") (pin "GND2") (pinfunction "GND_GND2") (pintype "bidirectional"))
      (node (ref "P4") (pin "T") (pinfunction "T_T") (pintype "bidirectional"))
      (node (ref "R15") (pin "1") (pinfunction "1_1") (pintype "passive"))
      (node (ref "R16") (pin "1") (pinfunction "1_1") (pintype "passive"))
      (node (ref "R17") (pin "1") (pinfunction "1_1") (pintype "passive"))
      (node (ref "R18") (pin "1") (pinfunction "1_1") (pintype "passive"))
      (node (ref "R7") (pin "2") (pinfunction "2_2") (pintype "passive"))
      (node (ref "S2") (pin "3") (pinfunction "OFF_3") (pintype "bidirectional"))
      (node (ref "U2") (pin "2") (pinfunction "VSS_2") (pintype "power_in"))
      (node (ref "U3") (pin "18") (pinfunction "GND18_18") (pintype "power_in"))
      (node (ref "U3") (pin "21") (pinfunction "GND21_21") (pintype "power_in"))
      (node (ref "U3") (pin "25") (pinfunction "AGND_25") (pintype "power_in"))
      (node (ref "U3") (pin "26") (pinfunction "TEST_26") (pintype "input"))
      (node (ref "U3") (pin "7") (pinfunction "GND7_7") (pintype "power_in"))
      (node (ref "U4") (pin "10") (pinfunction "AVSS_RFN_10") (pintype "bidirectional"))
      (node (ref "U4") (pin "11") (pinfunction "TST_11") (pintype "bidirectional"))
      (node (ref "U4") (pin "20") (pinfunction "DVSS_20") (pintype "bidirectional"))
      (node (ref "U4") (pin "24") (pinfunction "DVSS_24") (pintype "bidirectional"))
      (node (ref "U4") (pin "33") (pinfunction "CLKI_33") (pintype "bidirectional"))
      (node (ref "U4") (pin "35") (pinfunction "DVSS_35") (pintype "bidirectional"))
      (node (ref "U4") (pin "45") (pinfunction "DVSS_45") (pintype "bidirectional"))
      (node (ref "U4") (pin "55") (pinfunction "DVSS_55") (pintype "bidirectional"))
      (node (ref "U4") (pin "58") (pinfunction "AVSS_58") (pintype "bidirectional"))
      (node (ref "U4") (pin "61") (pinfunction "AVSS_61") (pintype "bidirectional"))
      (node (ref "U4") (pin "7") (pinfunction "AVSS_RFP_7") (pintype "bidirectional"))
      (node (ref "U5") (pin "8") (pinfunction "GND_8") (pintype "bidirectional"))
      (node (ref "V3") (pin "P1") (pinfunction "N_P1") (pintype "bidirectional"))
      (node (ref "V35") (pin "P1") (pinfunction "N_P1") (pintype "bidirectional"))
      (node (ref "V37") (pin "P1") (pinfunction "N_P1") (pintype "bidirectional"))
      (node (ref "V38") (pin "P1") (pinfunction "N_P1") (pintype "bidirectional"))
      (node (ref "V4") (pin "P1") (pinfunction "N_P1") (pintype "bidirectional"))
      (node (ref "V5") (pin "P1") (pinfunction "N_P1") (pintype "bidirectional"))
      (node (ref "V7") (pin "P1") (pinfunction "N_P1") (pintype "bidirectional"))
      (node (ref "V8") (pin "P1") (pinfunction "N_P1") (pintype "bidirectional"))
      (node (ref "V9") (pin "P1") (pinfunction "N_P1") (pintype "bidirectional"))
    )
    (net (code "18") (name "GREF") (class "Default")
      (node (ref "J2") (pin "1") (pinfunction "+_1") (pintype "bidirectional"))
      (node (ref "J2") (pin "4") (pinfunction "+_4") (pintype "bidirectional"))
      (node (ref "J3") (pin "1") (pinfunction "+_1") (pintype "bidirectional"))
      (node (ref "J3") (pin "4") (pinfunction "+_4") (pintype "bidirectional"))
      (node (ref "J7") (pin "1") (pinfunction "+_1") (pintype "bidirectional"))
      (node (ref "J7") (pin "4") (pinfunction "+_4") (pintype "bidirectional"))
      (node (ref "J8") (pin "1") (pinfunction "+_1") (pintype "bidirectional"))
      (node (ref "J8") (pin "4") (pinfunction "+_4") (pintype "bidirectional"))
      (node (ref "R8") (pin "1") (pinfunction "1_1") (pintype "passive"))
    )
    (net (code "19") (name "LCD_RX") (class "Default")
      (node (ref "L1") (pin "RXI") (pinfunction "RX_RXI") (pintype "bidirectional"))
      (node (ref "U4") (pin "32") (pinfunction "PD7(T0)_32") (pintype "bidirectional"))
    )
    (net (code "20") (name "LCD_TX") (class "Default")
      (node (ref "L1") (pin "TX0") (pinfunction "TX_TX0") (pintype "bidirectional"))
      (node (ref "U4") (pin "31") (pinfunction "PD6(T1)_31") (pintype "bidirectional"))
    )
    (net (code "21") (name "MISO") (class "Default")
      (node (ref "J4") (pin "1") (pinfunction "1_1") (pintype "passive"))
      (node (ref "U4") (pin "39") (pinfunction "PB3(MISO/PDO/PCINT3)_39") (pintype "bidirectional"))
    )
    (net (code "22") (name "MOSI") (class "Default")
      (node (ref "J4") (pin "4") (pinfunction "4_4") (pintype "passive"))
      (node (ref "U4") (pin "38") (pinfunction "PB2(MOSI/PDI/PCINT2)_38") (pintype "bidirectional"))
    )
    (net (code "23") (name "Net-(A1-SIGNAL)") (class "Default")
      (node (ref "A1") (pin "FEED") (pinfunction "SIGNAL_FEED") (pintype "bidirectional"))
      (node (ref "B2") (pin "1") (pinfunction "IN_1") (pintype "bidirectional"))
      (node (ref "C2") (pin "1") (pinfunction "1_1") (pintype "passive"))
    )
    (net (code "24") (name "Net-(B2-GND-Pad2)") (class "Default")
      (node (ref "B2") (pin "2") (pinfunction "GND_2") (pintype "bidirectional"))
      (node (ref "C3") (pin "2") (pinfunction "2_2") (pintype "passive"))
    )
    (net (code "25") (name "Net-(B2-OUT1)") (class "Default")
      (node (ref "B2") (pin "4") (pinfunction "OUT1_4") (pintype "bidirectional"))
      (node (ref "U4") (pin "8") (pinfunction "RFP_8") (pintype "bidirectional"))
    )
    (net (code "26") (name "Net-(B2-OUT2)") (class "Default")
      (node (ref "B2") (pin "3") (pinfunction "OUT2_3") (pintype "bidirectional"))
      (node (ref "U4") (pin "9") (pinfunction "RFN_9") (pintype "bidirectional"))
    )
    (net (code "27") (name "Net-(B11-P)") (class "Default")
      (node (ref "B11") (pin "2") (pinfunction "P_2") (pintype "bidirectional"))
      (node (ref "B3") (pin "1A") (pinfunction "P_1A") (pintype "bidirectional"))
      (node (ref "B3") (pin "1B") (pinfunction "P_1B") (pintype "bidirectional"))
      (node (ref "C6") (pin "1") (pinfunction "1_1") (pintype "passive"))
      (node (ref "D3") (pin "A") (pinfunction "A_A") (pintype "passive"))
      (node (ref "U2") (pin "3") (pinfunction "VBAT_3") (pintype "power_in"))
      (node (ref "V30") (pin "P1") (pinfunction "N_P1") (pintype "bidirectional"))
      (node (ref "V31") (pin "P1") (pinfunction "N_P1") (pintype "bidirectional"))
      (node (ref "V32") (pin "P1") (pinfunction "N_P1") (pintype "bidirectional"))
      (node (ref "V33") (pin "P1") (pinfunction "N_P1") (pintype "bidirectional"))
      (node (ref "V34") (pin "P1") (pinfunction "N_P1") (pintype "bidirectional"))
      (node (ref "V36") (pin "P1") (pinfunction "N_P1") (pintype "bidirectional"))
      (node (ref "V6") (pin "P1") (pinfunction "N_P1") (pintype "bidirectional"))
    )
    (net (code "28") (name "Net-(C11-Pad1)") (class "Default")
      (node (ref "C11") (pin "1") (pinfunction "1_1") (pintype "passive"))
      (node (ref "U4") (pin "21") (pinfunction "DVDD_21") (pintype "bidirectional"))
      (node (ref "U4") (pin "22") (pinfunction "DVDD_22") (pintype "bidirectional"))
    )
    (net (code "29") (name "Net-(D1-PadA1)") (class "Default")
      (node (ref "D1") (pin "A1") (pinfunction "A1_A1") (pintype "passive"))
      (node (ref "R3") (pin "1") (pinfunction "1_1") (pintype "passive"))
    )
    (net (code "30") (name "Net-(D1-PadC2)") (class "Default")
      (node (ref "D1") (pin "C2") (pinfunction "C2_C2") (pintype "passive"))
      (node (ref "R1") (pin "1") (pinfunction "1_1") (pintype "passive"))
    )
    (net (code "31") (name "Net-(D4-PadC1)") (class "Default")
      (node (ref "D4") (pin "C1") (pinfunction "C1_C1") (pintype "passive"))
      (node (ref "R15") (pin "2") (pinfunction "2_2") (pintype "passive"))
    )
    (net (code "32") (name "Net-(D4-PadC2)") (class "Default")
      (node (ref "D4") (pin "C2") (pinfunction "C2_C2") (pintype "passive"))
      (node (ref "R16") (pin "2") (pinfunction "2_2") (pintype "passive"))
    )
    (net (code "33") (name "Net-(D5-PadA1)") (class "Default")
      (node (ref "D5") (pin "A1") (pinfunction "A1_A1") (pintype "passive"))
      (node (ref "R14") (pin "1") (pinfunction "1_1") (pintype "passive"))
    )
    (net (code "34") (name "Net-(D5-PadA2)") (class "Default")
      (node (ref "D5") (pin "A2") (pinfunction "A2_A2") (pintype "passive"))
      (node (ref "R13") (pin "1") (pinfunction "1_1") (pintype "passive"))
    )
    (net (code "35") (name "Net-(D6-PadC1)") (class "Default")
      (node (ref "D6") (pin "C1") (pinfunction "C1_C1") (pintype "passive"))
      (node (ref "R18") (pin "2") (pinfunction "2_2") (pintype "passive"))
    )
    (net (code "36") (name "Net-(D6-PadC2)") (class "Default")
      (node (ref "D6") (pin "C2") (pinfunction "C2_C2") (pintype "passive"))
      (node (ref "R17") (pin "2") (pinfunction "2_2") (pintype "passive"))
    )
    (net (code "37") (name "Net-(S2-C)") (class "Default")
      (node (ref "S2") (pin "2") (pinfunction "C_2") (pintype "bidirectional"))
      (node (ref "U5") (pin "12") (pinfunction "2S_12") (pintype "bidirectional"))
      (node (ref "U5") (pin "4") (pinfunction "1S_4") (pintype "bidirectional"))
    )
    (net (code "38") (name "Net-(U2-PROG)") (class "Default")
      (node (ref "R7") (pin "1") (pinfunction "1_1") (pintype "passive"))
      (node (ref "U2") (pin "5") (pinfunction "PROG_5") (pintype "input"))
    )
    (net (code "39") (name "Net-(U2-STAT)") (class "Default")
      (node (ref "R1") (pin "2") (pinfunction "2_2") (pintype "passive"))
      (node (ref "R3") (pin "2") (pinfunction "2_2") (pintype "passive"))
      (node (ref "U2") (pin "1") (pinfunction "STAT_1") (pintype "output"))
    )
    (net (code "40") (name "Net-(U4-AVDD)") (class "Default")
      (node (ref "C13") (pin "1") (pinfunction "1_1") (pintype "passive"))
      (node (ref "U4") (pin "60") (pinfunction "AVDD_60") (pintype "bidirectional"))
    )
    (net (code "41") (name "Net-(U4-PG0(DIG3))") (class "Default")
      (node (ref "D6") (pin "A2") (pinfunction "A2_A2") (pintype "passive"))
      (node (ref "U4") (pin "14") (pinfunction "PG0(DIG3)_14") (pintype "bidirectional"))
    )
    (net (code "42") (name "Net-(U4-PG1(DIG1))") (class "Default")
      (node (ref "D6") (pin "A1") (pinfunction "A1_A1") (pintype "passive"))
      (node (ref "U4") (pin "15") (pinfunction "PG1(DIG1)_15") (pintype "bidirectional"))
    )
    (net (code "43") (name "Net-(U4-XTAL1)") (class "Default")
      (node (ref "C14") (pin "1") (pinfunction "1_1") (pintype "passive"))
      (node (ref "U4") (pin "57") (pinfunction "XTAL1_57") (pintype "bidirectional"))
      (node (ref "Y1") (pin "3") (pinfunction "2_3") (pintype "passive"))
    )
    (net (code "44") (name "Net-(U4-XTAL2)") (class "Default")
      (node (ref "C15") (pin "1") (pinfunction "1_1") (pintype "passive"))
      (node (ref "U4") (pin "56") (pinfunction "XTAL2_56") (pintype "bidirectional"))
      (node (ref "Y1") (pin "1") (pinfunction "1_1") (pintype "passive"))
    )
    (net (code "45") (name "PITCH") (class "Default")
      (node (ref "J3") (pin "V") (pinfunction "V_V") (pintype "bidirectional"))
      (node (ref "J8") (pin "V") (pinfunction "V_V") (pintype "bidirectional"))
      (node (ref "U4") (pin "2") (pinfunction "PF3(ADC3/DIG4)_2") (pintype "bidirectional"))
    )
    (net (code "46") (name "RESET") (class "Default")
      (node (ref "B1") (pin "1") (pinfunction "1_1") (pintype "passive"))
      (node (ref "B1") (pin "2") (pinfunction "1_2") (pintype "passive"))
      (node (ref "C1") (pin "1") (pinfunction "1_1") (pintype "passive"))
      (node (ref "J4") (pin "5") (pinfunction "5_5") (pintype "passive"))
      (node (ref "R2") (pin "1") (pinfunction "1_1") (pintype "passive"))
      (node (ref "U4") (pin "12") (pinfunction "RSTN_12") (pintype "bidirectional"))
    )
    (net (code "47") (name "RF") (class "Default")
      (node (ref "D4") (pin "A1") (pinfunction "A1_A1") (pintype "passive"))
      (node (ref "U4") (pin "16") (pinfunction "PG2(AMR)_16") (pintype "bidirectional"))
    )
    (net (code "48") (name "ROLL") (class "Default")
      (node (ref "J3") (pin "H") (pinfunction "H_H") (pintype "bidirectional"))
      (node (ref "J8") (pin "H") (pinfunction "H_H") (pintype "bidirectional"))
      (node (ref "U4") (pin "1") (pinfunction "PF2(ADC2/DIG2)_1") (pintype "bidirectional"))
    )
    (net (code "49") (name "RXI") (class "Default")
      (node (ref "U3") (pin "5") (pinfunction "RXD_5") (pintype "input"))
      (node (ref "U5") (pin "10") (pinfunction "3Z_10") (pintype "bidirectional"))
    )
    (net (code "50") (name "RXI-0") (class "Default")
      (node (ref "U4") (pin "47") (pinfunction "PE1(TXD0)_47") (pintype "bidirectional"))
      (node (ref "U5") (pin "11") (pinfunction "3Y0_11") (pintype "bidirectional"))
    )
    (net (code "51") (name "RXI-1") (class "Default")
      (node (ref "JP1") (pin "RXI") (pinfunction "2_RXI") (pintype "passive"))
      (node (ref "U5") (pin "9") (pinfunction "3Y1_9") (pintype "bidirectional"))
    )
    (net (code "52") (name "RXLED") (class "Default")
      (node (ref "D5") (pin "C2") (pinfunction "C2_C2") (pintype "passive"))
      (node (ref "U3") (pin "22") (pinfunction "RXLED_22") (pintype "input"))
    )
    (net (code "53") (name "SCK") (class "Default")
      (node (ref "J4") (pin "3") (pinfunction "3_3") (pintype "passive"))
      (node (ref "U4") (pin "37") (pinfunction "PB1(SCK/PCINT1)_37") (pintype "bidirectional"))
    )
    (net (code "54") (name "THROTTLE") (class "Default")
      (node (ref "J2") (pin "V") (pinfunction "V_V") (pintype "bidirectional"))
      (node (ref "J7") (pin "V") (pinfunction "V_V") (pintype "bidirectional"))
      (node (ref "U4") (pin "64") (pinfunction "PF1(ADC1)_64") (pintype "bidirectional"))
    )
    (net (code "55") (name "TXLED") (class "Default")
      (node (ref "D5") (pin "C1") (pinfunction "C1_C1") (pintype "passive"))
      (node (ref "U3") (pin "23") (pinfunction "TXLED_23") (pintype "input"))
    )
    (net (code "56") (name "TXO") (class "Default")
      (node (ref "U3") (pin "1") (pinfunction "TXD_1") (pintype "output"))
      (node (ref "U5") (pin "6") (pinfunction "2Z_6") (pintype "bidirectional"))
    )
    (net (code "57") (name "TXO-0") (class "Default")
      (node (ref "U4") (pin "46") (pinfunction "PE0(RXD0/PCINT8)_46") (pintype "bidirectional"))
      (node (ref "U5") (pin "7") (pinfunction "2Y0_7") (pintype "bidirectional"))
    )
    (net (code "58") (name "TXO-1") (class "Default")
      (node (ref "JP1") (pin "TXO") (pinfunction "3_TXO") (pintype "passive"))
      (node (ref "U5") (pin "5") (pinfunction "2Y1_5") (pintype "bidirectional"))
    )
    (net (code "59") (name "USB_D_N") (class "Default")
      (node (ref "J1") (pin "2") (pinfunction "2-D-_2") (pintype "bidirectional"))
      (node (ref "U3") (pin "16") (pinfunction "USBDM_16") (pintype "bidirectional"))
    )
    (net (code "60") (name "USB_D_P") (class "Default")
      (node (ref "J1") (pin "3") (pinfunction "3-D+_3") (pintype "bidirectional"))
      (node (ref "U3") (pin "15") (pinfunction "USBDP_15") (pintype "bidirectional"))
    )
    (net (code "61") (name "VBAT") (class "Default")
      (node (ref "D2") (pin "C") (pinfunction "C_C") (pintype "passive"))
      (node (ref "D3") (pin "C") (pinfunction "C_C") (pintype "passive"))
      (node (ref "P2") (pin "T") (pinfunction "T_T") (pintype "bidirectional"))
      (node (ref "S1") (pin "2") (pinfunction "C_2") (pintype "bidirectional"))
      (node (ref "V10") (pin "P1") (pinfunction "N_P1") (pintype "bidirectional"))
    )
    (net (code "62") (name "VBUS") (class "Default")
      (node (ref "C5") (pin "1") (pinfunction "1_1") (pintype "passive"))
      (node (ref "D1") (pin "A2") (pinfunction "A2_A2") (pintype "passive"))
      (node (ref "D2") (pin "A") (pinfunction "A_A") (pintype "passive"))
      (node (ref "J1") (pin "1") (pinfunction "1-VCC_1") (pintype "bidirectional"))
      (node (ref "P1") (pin "T") (pinfunction "T_T") (pintype "bidirectional"))
      (node (ref "U2") (pin "4") (pinfunction "VDD_4") (pintype "power_in"))
      (node (ref "V1") (pin "P1") (pinfunction "N_P1") (pintype "bidirectional"))
      (node (ref "V2") (pin "P1") (pinfunction "N_P1") (pintype "bidirectional"))
      (node (ref "V23") (pin "P1") (pinfunction "N_P1") (pintype "bidirectional"))
      (node (ref "V24") (pin "P1") (pinfunction "N_P1") (pintype "bidirectional"))
      (node (ref "V26") (pin "P1") (pinfunction "N_P1") (pintype "bidirectional"))
      (node (ref "V27") (pin "P1") (pinfunction "N_P1") (pintype "bidirectional"))
      (node (ref "V28") (pin "P1") (pinfunction "N_P1") (pintype "bidirectional"))
    )
    (net (code "63") (name "VREG_IN") (class "Default")
      (node (ref "C7") (pin "1") (pinfunction "1_1") (pintype "passive"))
      (node (ref "C8") (pin "1") (pinfunction "1_1") (pintype "passive"))
      (node (ref "L1") (pin "RAW") (pinfunction "VIN_RAW") (pintype "bidirectional"))
      (node (ref "S1") (pin "1") (pinfunction "ON_1") (pintype "bidirectional"))
      (node (ref "U3") (pin "20") (pinfunction "VCC_20") (pintype "power_in"))
    )
    (net (code "64") (name "YAW") (class "Default")
      (node (ref "J2") (pin "H") (pinfunction "H_H") (pintype "bidirectional"))
      (node (ref "J7") (pin "H") (pinfunction "H_H") (pintype "bidirectional"))
      (node (ref "U4") (pin "63") (pinfunction "PF0(ADC0)_63") (pintype "bidirectional"))
    )
    (net (code "65") (name "unconnected-(J1-4-ID-Pad4)") (class "Default")
      (node (ref "J1") (pin "4") (pinfunction "4-ID_4") (pintype "bidirectional"))
    )
    (net (code "66") (name "unconnected-(L1-PadSCK)") (class "Default")
      (node (ref "L1") (pin "SCK") (pinfunction "SCK_SCK") (pintype "bidirectional"))
    )
    (net (code "67") (name "unconnected-(L1-PadSDI)") (class "Default")
      (node (ref "L1") (pin "SDI") (pinfunction "SDI_SDI") (pintype "bidirectional"))
    )
    (net (code "68") (name "unconnected-(L1-PadSDO)") (class "Default")
      (node (ref "L1") (pin "SDO") (pinfunction "SDO_SDO") (pintype "bidirectional"))
    )
    (net (code "69") (name "unconnected-(L1-Pad{slash}CS)") (class "Default")
      (node (ref "L1") (pin "/CS") (pinfunction "/CS_/CS") (pintype "bidirectional"))
    )
    (net (code "70") (name "unconnected-(L1-SCL-PadCL)") (class "Default")
      (node (ref "L1") (pin "CL") (pinfunction "SCL_CL") (pintype "bidirectional"))
    )
    (net (code "71") (name "unconnected-(L1-SDA-PadDA)") (class "Default")
      (node (ref "L1") (pin "DA") (pinfunction "SDA_DA") (pintype "bidirectional"))
    )
    (net (code "72") (name "unconnected-(S1-OFF-Pad3)") (class "Default")
      (node (ref "S1") (pin "3") (pinfunction "OFF_3") (pintype "bidirectional"))
    )
    (net (code "73") (name "unconnected-(U3-DCD-Pad10)") (class "Default")
      (node (ref "U3") (pin "10") (pinfunction "DCD_10") (pintype "input"))
    )
    (net (code "74") (name "unconnected-(U3-DSR-Pad9)") (class "Default")
      (node (ref "U3") (pin "9") (pinfunction "DSR_9") (pintype "input"))
    )
    (net (code "75") (name "unconnected-(U3-OSCI-Pad27)") (class "Default")
      (node (ref "U3") (pin "27") (pinfunction "OSCI_27") (pintype "input"))
    )
    (net (code "76") (name "unconnected-(U3-OSCO-Pad28)") (class "Default")
      (node (ref "U3") (pin "28") (pinfunction "OSCO_28") (pintype "output"))
    )
    (net (code "77") (name "unconnected-(U3-PWREN-Pad14)") (class "Default")
      (node (ref "U3") (pin "14") (pinfunction "PWREN_14") (pintype "input"))
    )
    (net (code "78") (name "unconnected-(U3-RESET-Pad19)") (class "Default")
      (node (ref "U3") (pin "19") (pinfunction "RESET_19") (pintype "input"))
    )
    (net (code "79") (name "unconnected-(U3-RI-Pad6)") (class "Default")
      (node (ref "U3") (pin "6") (pinfunction "RI_6") (pintype "input"))
    )
    (net (code "80") (name "unconnected-(U3-RTS-Pad3)") (class "Default")
      (node (ref "U3") (pin "3") (pinfunction "RTS_3") (pintype "output"))
    )
    (net (code "81") (name "unconnected-(U3-SLEEP-Pad12)") (class "Default")
      (node (ref "U3") (pin "12") (pinfunction "SLEEP_12") (pintype "input"))
    )
    (net (code "82") (name "unconnected-(U3-TXDEN-Pad13)") (class "Default")
      (node (ref "U3") (pin "13") (pinfunction "TXDEN_13") (pintype "input"))
    )
    (net (code "83") (name "unconnected-(U4-AREF-Pad62)") (class "Default")
      (node (ref "U4") (pin "62") (pinfunction "AREF_62") (pintype "bidirectional"))
    )
    (net (code "84") (name "unconnected-(U4-PB0(SSN{slash}PCINT0)-Pad36)") (class "Default")
      (node (ref "U4") (pin "36") (pinfunction "PB0(SSN/PCINT0)_36") (pintype "bidirectional"))
    )
    (net (code "85") (name "unconnected-(U4-PB6(OC1B{slash}PCINT6)-Pad42)") (class "Default")
      (node (ref "U4") (pin "42") (pinfunction "PB6(OC1B/PCINT6)_42") (pintype "bidirectional"))
    )
    (net (code "86") (name "unconnected-(U4-PB7(OC0A{slash}OC1C{slash}PCINT7)-Pad43)") (class "Default")
      (node (ref "U4") (pin "43") (pinfunction "PB7(OC0A/OC1C/PCINT7)_43") (pintype "bidirectional"))
    )
    (net (code "87") (name "unconnected-(U4-PD4(ICP1)-Pad29)") (class "Default")
      (node (ref "U4") (pin "29") (pinfunction "PD4(ICP1)_29") (pintype "bidirectional"))
    )
    (net (code "88") (name "unconnected-(U4-PD5(XCK1)-Pad30)") (class "Default")
      (node (ref "U4") (pin "30") (pinfunction "PD5(XCK1)_30") (pintype "bidirectional"))
    )
    (net (code "89") (name "unconnected-(U4-PE2(XCK0{slash}AIN0)-Pad48)") (class "Default")
      (node (ref "U4") (pin "48") (pinfunction "PE2(XCK0/AIN0)_48") (pintype "bidirectional"))
    )
    (net (code "90") (name "unconnected-(U4-PE3(OC3A{slash}AIN1)-Pad49)") (class "Default")
      (node (ref "U4") (pin "49") (pinfunction "PE3(OC3A/AIN1)_49") (pintype "bidirectional"))
    )
    (net (code "91") (name "unconnected-(U4-PF4(ADC4{slash}TCK)-Pad3)") (class "Default")
      (node (ref "U4") (pin "3") (pinfunction "PF4(ADC4/TCK)_3") (pintype "bidirectional"))
    )
    (net (code "92") (name "unconnected-(U4-PF5(ADC5{slash}TMS)-Pad4)") (class "Default")
      (node (ref "U4") (pin "4") (pinfunction "PF5(ADC5/TMS)_4") (pintype "bidirectional"))
    )
    (net (code "93") (name "unconnected-(U4-PF6(ADC6{slash}TDO)-Pad5)") (class "Default")
      (node (ref "U4") (pin "5") (pinfunction "PF6(ADC6/TDO)_5") (pintype "bidirectional"))
    )
    (net (code "94") (name "unconnected-(U4-PF7(ADC7{slash}TDI)-Pad6)") (class "Default")
      (node (ref "U4") (pin "6") (pinfunction "PF7(ADC7/TDI)_6") (pintype "bidirectional"))
    )
    (net (code "95") (name "unconnected-(U4-PG3(TOSC2)-Pad17)") (class "Default")
      (node (ref "U4") (pin "17") (pinfunction "PG3(TOSC2)_17") (pintype "bidirectional"))
    )
    (net (code "96") (name "unconnected-(U4-PG4(TOSC1)-Pad18)") (class "Default")
      (node (ref "U4") (pin "18") (pinfunction "PG4(TOSC1)_18") (pintype "bidirectional"))
    )
    (net (code "97") (name "unconnected-(U4-PG5(OC0B)-Pad19)") (class "Default")
      (node (ref "U4") (pin "19") (pinfunction "PG5(OC0B)_19") (pintype "bidirectional"))
    )
    (net (code "98") (name "unconnected-(U4-RSTON-Pad13)") (class "Default")
      (node (ref "U4") (pin "13") (pinfunction "RSTON_13") (pintype "bidirectional"))
    )
    (net (code "99") (name "unconnected-(U5-1Y0-Pad3)") (class "Default")
      (node (ref "U5") (pin "3") (pinfunction "1Y0_3") (pintype "bidirectional"))
    )
  )
)
